# uMultimeter_ExpDigiPower_Sch.net
KiCad netlist of a schematic drawn in Altium Designer
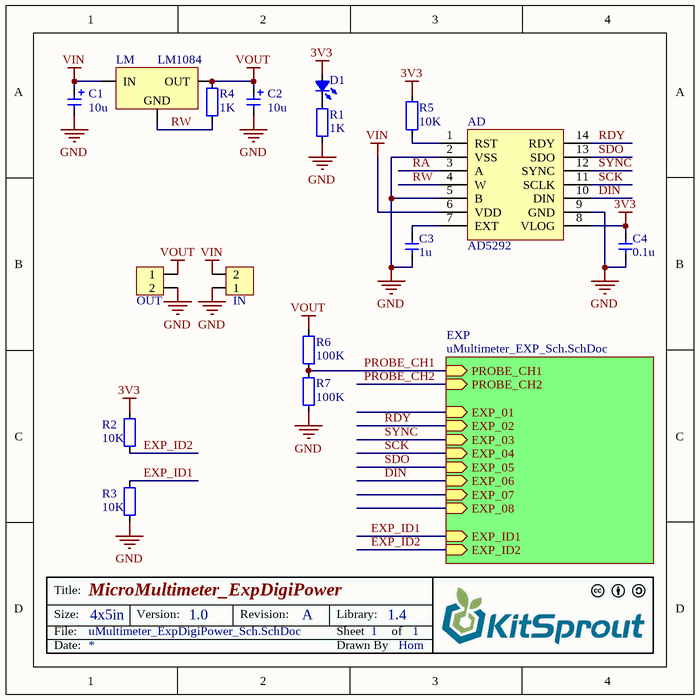
[diagram p0: uMultimeter_ExpDigiPower_Sch.SchDoc]

(export (version "E")
  (design (tool "Eeschema 10.0.6"))
  (components
    (comp (ref "AD")
      (value "AD5292")
      (footprint "PCB_IntegratedCircuit:TSSOP_E170_P0.65_14")
      (description "Digital Pot")
      (libsource (lib "SCH_IntegratedCircuit") (part "AD5292"))
    )
    (comp (ref "C1")
      (value "10u")
      (footprint "PCB_PassiveCap:CAP_TAN_B1210")
      (description "Capacitor")
      (fields (field (name "Comment") "Cap_Tan_1210"))
      (libsource (lib "SCH_Passive") (part "Cap_Tan_1210"))
    )
    (comp (ref "C2")
      (value "10u")
      (footprint "PCB_PassiveCap:CAP_TAN_B1210")
      (description "Capacitor")
      (fields (field (name "Comment") "Cap_Tan_1210"))
      (libsource (lib "SCH_Passive") (part "Cap_Tan_1210"))
    )
    (comp (ref "C3")
      (value "1u")
      (footprint "PCB_PassiveCap:CAP_0603")
      (description "Capacitor")
      (fields (field (name "Comment") "Cap_0603"))
      (libsource (lib "SCH_Passive") (part "Cap_0603"))
    )
    (comp (ref "C4")
      (value "0.1u")
      (footprint "PCB_PassiveCap:CAP_0603")
      (description "Capacitor")
      (fields (field (name "Comment") "Cap_0603"))
      (libsource (lib "SCH_Passive") (part "Cap_0603"))
    )
    (comp (ref "D1")
      (value "LED_0805")
      (footprint "PCB_ActiveLED:LED_0805_BLUE")
      (description "LED")
      (libsource (lib "SCH_Active") (part "LED_0805"))
    )
    (comp (ref "IN")
      (value "2Way_5")
      (footprint "PCB_ConnectorCable:2Way_5")
      (description "DB")
      (libsource (lib "") (part "2Way_5_1"))
    )
    (comp (ref "LM")
      (value "LM1084")
      (footprint "PCB_IntegratedCircuit:TO-263-3")
      (description "Power")
      (libsource (lib "SCH_IntegratedCircuit") (part "LM1084"))
    )
    (comp (ref "OUT")
      (value "2Way_5")
      (footprint "PCB_ConnectorCable:2Way_5")
      (description "DB")
      (libsource (lib "SCH_Connector") (part "2Way_5"))
    )
    (comp (ref "R1")
      (value "1K")
      (footprint "PCB_PassiveRes:RES_0603")
      (description "Resistor")
      (fields (field (name "Comment") "Res_0603"))
      (libsource (lib "SCH_Passive") (part "Res_0603"))
    )
    (comp (ref "R2")
      (value "10K")
      (footprint "PCB_PassiveRes:RES_0603")
      (description "Resistor")
      (fields (field (name "Comment") "Res_0603"))
      (libsource (lib "SCH_Passive") (part "Res_0603"))
    )
    (comp (ref "R3")
      (value "10K")
      (footprint "PCB_PassiveRes:RES_0603")
      (description "Resistor")
      (fields (field (name "Comment") "Res_0603"))
      (libsource (lib "SCH_Passive") (part "Res_0603"))
    )
    (comp (ref "R4")
      (value "1K")
      (footprint "PCB_PassiveRes:RES_0603")
      (description "Resistor")
      (fields (field (name "Comment") "Res_0603"))
      (libsource (lib "") (part "Res_0603_1"))
    )
    (comp (ref "R5")
      (value "10K")
      (footprint "PCB_PassiveRes:RES_0603")
      (description "Resistor")
      (fields (field (name "Comment") "Res_0603"))
      (libsource (lib "") (part "Res_0603_1"))
    )
    (comp (ref "R6")
      (value "100K")
      (footprint "PCB_PassiveRes:RES_0603")
      (description "Resistor")
      (fields (field (name "Comment") "Res_0603"))
      (libsource (lib "") (part "Res_0603_1"))
    )
    (comp (ref "R7")
      (value "100K")
      (footprint "PCB_PassiveRes:RES_0603")
      (description "Resistor")
      (fields (field (name "Comment") "Res_0603"))
      (libsource (lib "") (part "Res_0603_1"))
    )
  )
  (nets
    (net (code "1") (name "/DIN") (class "Default")
      (node (ref "AD") (pin "10") (pinfunction "DIN_10") (pintype "passive"))
    )
    (net (code "5") (name "/EXP_ID1") (class "Default")
      (node (ref "R3") (pin "1") (pinfunction "1_1") (pintype "passive"))
    )
    (net (code "6") (name "/EXP_ID2") (class "Default")
      (node (ref "R2") (pin "2") (pinfunction "2_2") (pintype "passive"))
    )
    (net (code "7") (name "/PROBE_CH1") (class "Default")
      (node (ref "R6") (pin "1") (pinfunction "1_1") (pintype "passive"))
      (node (ref "R7") (pin "2") (pinfunction "2_2") (pintype "passive"))
    )
    (net (code "9") (name "/RA") (class "Default")
      (node (ref "AD") (pin "3") (pinfunction "A_3") (pintype "passive"))
    )
    (net (code "10") (name "/RDY") (class "Default")
      (node (ref "AD") (pin "14") (pinfunction "RDY_14") (pintype "passive"))
    )
    (net (code "11") (name "/RW") (class "Default")
      (node (ref "AD") (pin "4") (pinfunction "W_4") (pintype "passive"))
      (node (ref "LM") (pin "1") (pinfunction "ADJ_1") (pintype "power_in"))
      (node (ref "R4") (pin "1") (pinfunction "1_1") (pintype "passive"))
    )
    (net (code "12") (name "/SCK") (class "Default")
      (node (ref "AD") (pin "11") (pinfunction "SCLK_11") (pintype "passive"))
    )
    (net (code "13") (name "/SDO") (class "Default")
      (node (ref "AD") (pin "13") (pinfunction "SDO_13") (pintype "passive"))
    )
    (net (code "14") (name "/SYNC") (class "Default")
      (node (ref "AD") (pin "12") (pinfunction "SYNC_12") (pintype "passive"))
    )
    (net (code "15") (name "3V3") (class "Default")
      (node (ref "AD") (pin "8") (pinfunction "VLOG_8") (pintype "passive"))
      (node (ref "C4") (pin "2") (pinfunction "2_2") (pintype "passive"))
      (node (ref "D1") (pin "1") (pinfunction "A_1") (pintype "passive"))
      (node (ref "R2") (pin "1") (pinfunction "1_1") (pintype "passive"))
      (node (ref "R5") (pin "2") (pinfunction "2_2") (pintype "passive"))
    )
    (net (code "16") (name "GND") (class "Default")
      (node (ref "AD") (pin "2") (pinfunction "VSS_2") (pintype "passive"))
      (node (ref "AD") (pin "5") (pinfunction "B_5") (pintype "passive"))
      (node (ref "AD") (pin "9") (pinfunction "GND_9") (pintype "passive"))
      (node (ref "C1") (pin "2") (pinfunction "2_2") (pintype "passive"))
      (node (ref "C2") (pin "2") (pinfunction "2_2") (pintype "passive"))
      (node (ref "C3") (pin "1") (pinfunction "1_1") (pintype "passive"))
      (node (ref "C4") (pin "1") (pinfunction "1_1") (pintype "passive"))
      (node (ref "IN") (pin "1") (pinfunction "1_1") (pintype "passive"))
      (node (ref "OUT") (pin "2") (pinfunction "2_2") (pintype "passive"))
      (node (ref "R1") (pin "2") (pinfunction "2_2") (pintype "passive"))
      (node (ref "R3") (pin "2") (pinfunction "2_2") (pintype "passive"))
      (node (ref "R7") (pin "1") (pinfunction "1_1") (pintype "passive"))
    )
    (net (code "17") (name "Net-(AD-EXT)") (class "Default")
      (node (ref "AD") (pin "7") (pinfunction "EXT_7") (pintype "passive"))
      (node (ref "C3") (pin "2") (pinfunction "2_2") (pintype "passive"))
    )
    (net (code "18") (name "Net-(AD-RST)") (class "Default")
      (node (ref "AD") (pin "1") (pinfunction "RST_1") (pintype "passive"))
      (node (ref "R5") (pin "1") (pinfunction "1_1") (pintype "passive"))
    )
    (net (code "19") (name "Net-(D1-K)") (class "Default")
      (node (ref "D1") (pin "2") (pinfunction "K_2") (pintype "passive"))
      (node (ref "R1") (pin "1") (pinfunction "1_1") (pintype "passive"))
    )
    (net (code "20") (name "VIN") (class "Default")
      (node (ref "AD") (pin "6") (pinfunction "VDD_6") (pintype "passive"))
      (node (ref "C1") (pin "1") (pinfunction "1_1") (pintype "passive"))
      (node (ref "IN") (pin "2") (pinfunction "2_2") (pintype "passive"))
      (node (ref "LM") (pin "3") (pinfunction "IN_3") (pintype "power_in"))
    )
    (net (code "21") (name "VOUT") (class "Default")
      (node (ref "C2") (pin "1") (pinfunction "1_1") (pintype "passive"))
      (node (ref "LM") (pin "2") (pinfunction "OUT_2") (pintype "power_in"))
      (node (ref "OUT") (pin "1") (pinfunction "1_1") (pintype "passive"))
      (node (ref "R4") (pin "2") (pinfunction "2_2") (pintype "passive"))
      (node (ref "R6") (pin "2") (pinfunction "2_2") (pintype "passive"))
    )
  )
)
